# RF_Switch.net
KiCad netlist of a schematic drawn in Altium Designer
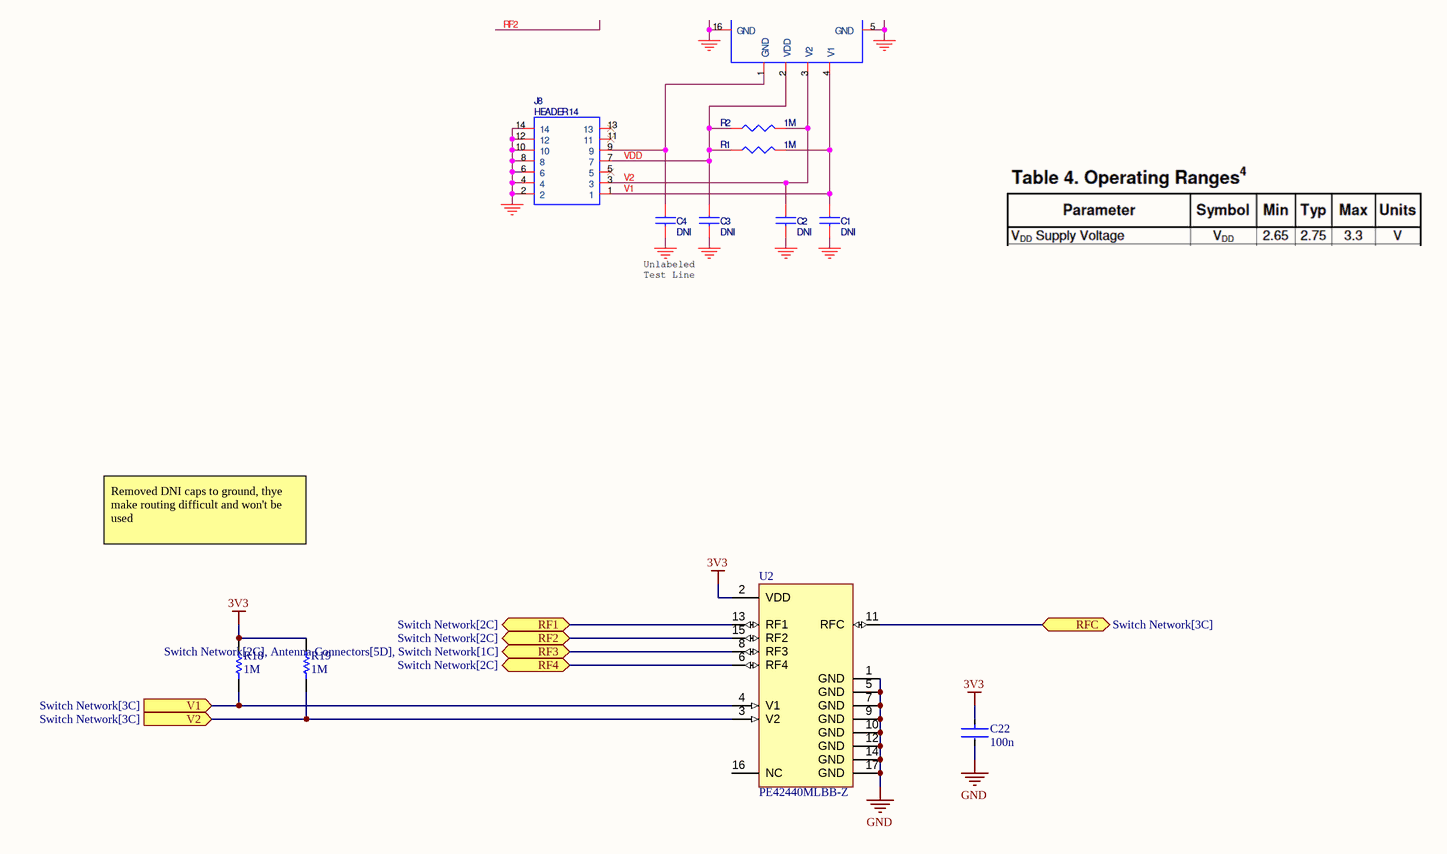
[diagram p0: RF Switch.SchDoc]

(export (version "E")
  (design (tool "Eeschema 10.0.6"))
  (components
    (comp (ref "C22")
      (value "100n")
      (footprint "FP-0603-Capacitor-CL10-IPC_B")
      (description "CAP CER 50V X7R 0603")
      (fields (field (name "TOLERANCE") "0.1") (field (name "MANUFACTURER") "KEMET"))
      (libsource (lib "CBU-PCB") (part "Ceramic Capacitor 0603"))
    )
    (comp (ref "R18")
      (value "1M")
      (footprint "RESC1608X55X25NL10T15")
      (fields
        (field (name "TOLERANCE") "1%")
        (field (name "MANUFACTURER") "Yageo")
        (field (name "Comment") "RC0603FR-072K2L")
      )
      (libsource (lib "CBU-PCB") (part "Resistor 0603"))
    )
    (comp (ref "R19")
      (value "1M")
      (footprint "RESC1608X55X25NL10T15")
      (fields
        (field (name "TOLERANCE") "1%")
        (field (name "MANUFACTURER") "Yageo")
        (field (name "Comment") "RC0603FR-072K2L")
      )
      (libsource (lib "CBU-PCB") (part "Resistor 0603"))
    )
    (comp (ref "U2")
      (value "PE42440MLBB-Z")
      (footprint "PE42440MLBB-Z")
      (description "RF Switch IC General Purpose SP4T 3 GHz 50Ohm 16-QFN (3x3)")
      (libsource (lib "CBU-PCB") (part "PE42440MLBB-Z"))
    )
  )
  (nets
    (net (code "1") (name "/RF1") (class "Default")
      (node (ref "U2") (pin "13") (pinfunction "RF1_13") (pintype "bidirectional"))
    )
    (net (code "2") (name "/RF2") (class "Default")
      (node (ref "U2") (pin "15") (pinfunction "RF2_15") (pintype "bidirectional"))
    )
    (net (code "3") (name "/RF3") (class "Default")
      (node (ref "U2") (pin "8") (pinfunction "RF3_8") (pintype "bidirectional"))
    )
    (net (code "4") (name "/RF4") (class "Default")
      (node (ref "U2") (pin "6") (pinfunction "RF4_6") (pintype "bidirectional"))
    )
    (net (code "5") (name "/RFC") (class "Default")
      (node (ref "U2") (pin "11") (pinfunction "RFC_11") (pintype "bidirectional"))
    )
    (net (code "6") (name "/V1") (class "Default")
      (node (ref "R18") (pin "1") (pinfunction "1_1") (pintype "passive"))
      (node (ref "U2") (pin "4") (pinfunction "V1_4") (pintype "input"))
    )
    (net (code "7") (name "/V2") (class "Default")
      (node (ref "R19") (pin "1") (pinfunction "1_1") (pintype "passive"))
      (node (ref "U2") (pin "3") (pinfunction "V2_3") (pintype "input"))
    )
    (net (code "8") (name "3V3") (class "Default")
      (node (ref "C22") (pin "1") (pinfunction "1_1") (pintype "passive"))
      (node (ref "R18") (pin "2") (pinfunction "2_2") (pintype "passive"))
      (node (ref "R19") (pin "2") (pinfunction "2_2") (pintype "passive"))
      (node (ref "U2") (pin "2") (pinfunction "VDD_2") (pintype "power_in"))
    )
    (net (code "9") (name "GND") (class "Default")
      (node (ref "C22") (pin "2") (pinfunction "2_2") (pintype "passive"))
      (node (ref "U2") (pin "1") (pinfunction "GND_1") (pintype "power_in"))
      (node (ref "U2") (pin "10") (pinfunction "GND_10") (pintype "power_in"))
      (node (ref "U2") (pin "12") (pinfunction "GND_12") (pintype "power_in"))
      (node (ref "U2") (pin "14") (pinfunction "GND_14") (pintype "power_in"))
      (node (ref "U2") (pin "17") (pinfunction "GND_17") (pintype "power_in"))
      (node (ref "U2") (pin "5") (pinfunction "GND_5") (pintype "power_in"))
      (node (ref "U2") (pin "7") (pinfunction "GND_7") (pintype "power_in"))
      (node (ref "U2") (pin "9") (pinfunction "GND_9") (pintype "power_in"))
    )
    (net (code "10") (name "unconnected-(U2-NC-Pad16)") (class "Default")
      (node (ref "U2") (pin "16") (pinfunction "NC_16") (pintype "passive"))
    )
  )
)
